# PCB_Capacitor.net
KiCad netlist of a schematic drawn in EAGLE
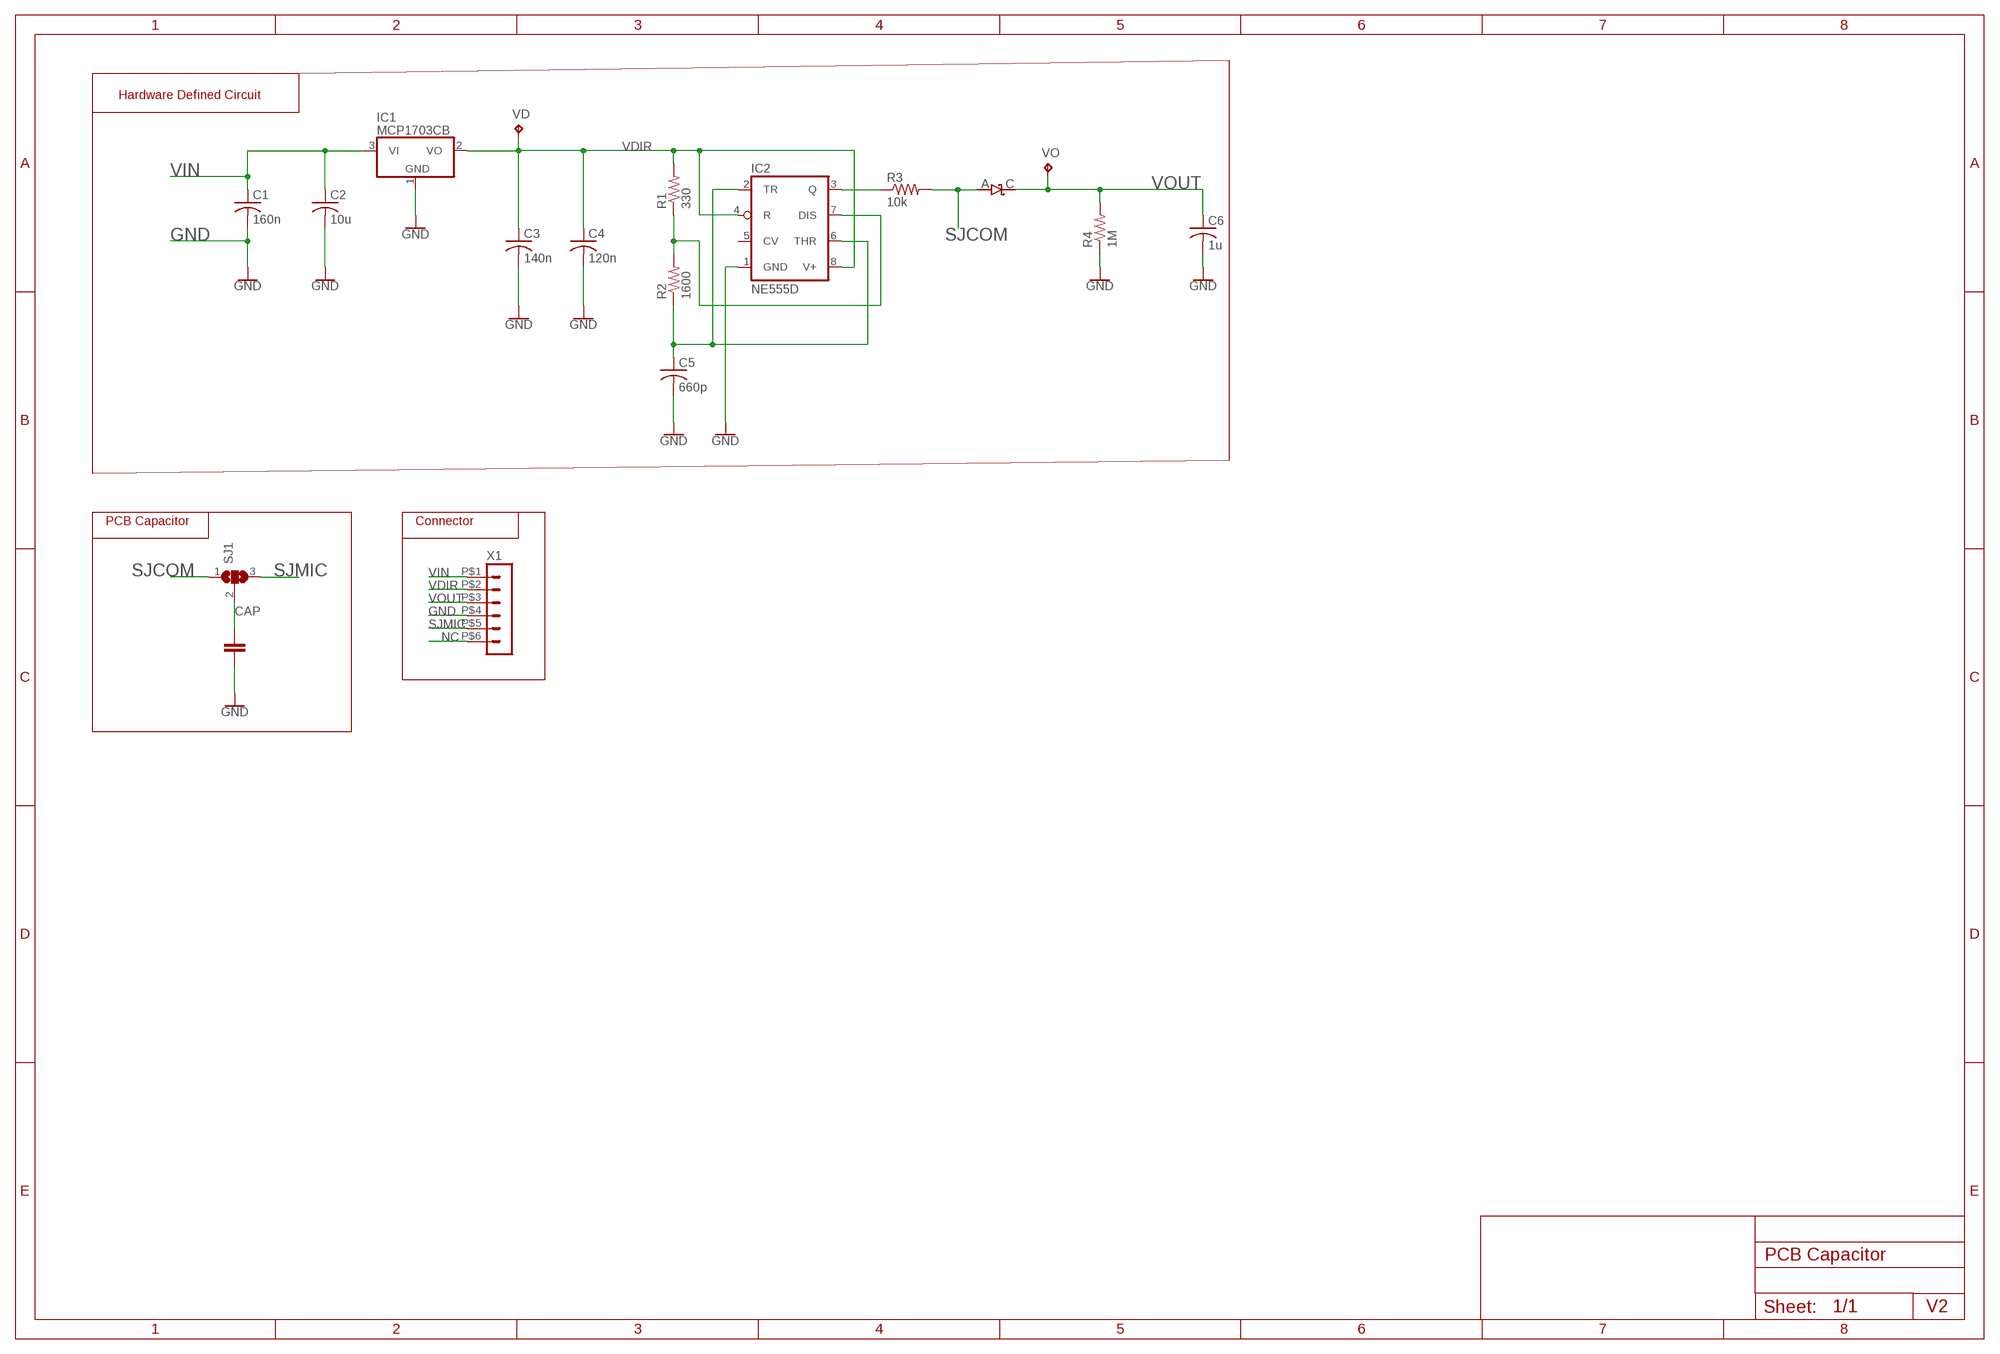
[diagram p0: schematic, sheet 1]

(export (version "E")
  (design (tool "Eeschema 10.0.6"))
  (components
    (comp (ref "C1")
      (value "160n")
      (footprint "eagle-import:C0805")
      (libsource (lib "eagle-import") (part "C-USC0805"))
    )
    (comp (ref "C2")
      (value "10u")
      (footprint "eagle-import:C0805")
      (libsource (lib "eagle-import") (part "C-USC0805"))
    )
    (comp (ref "C3")
      (value "140n")
      (footprint "eagle-import:C0805")
      (libsource (lib "eagle-import") (part "C-USC0805"))
    )
    (comp (ref "C4")
      (value "120n")
      (footprint "eagle-import:C0805")
      (libsource (lib "eagle-import") (part "C-USC0805"))
    )
    (comp (ref "C5")
      (value "660p")
      (footprint "eagle-import:C0805")
      (libsource (lib "eagle-import") (part "C-USC0805"))
    )
    (comp (ref "C6")
      (value "1u")
      (footprint "eagle-import:C0805")
      (libsource (lib "eagle-import") (part "C-USC0805"))
    )
    (comp (ref "D11")
      (value "DIODE_SCHOTTKY_CMMSH2-40")
      (footprint "eagle-import:SOD-123")
      (libsource (lib "eagle-import") (part "DIODE_SCHOTTKY_CMMSH2-40"))
    )
    (comp (ref "IC1")
      (value "MCP1703CB")
      (footprint "eagle-import:SOT23")
      (libsource (lib "eagle-import") (part "MCP1703CB"))
    )
    (comp (ref "IC2")
      (value "NE555D")
      (footprint "eagle-import:SO08")
      (libsource (lib "eagle-import") (part "555DNE"))
    )
    (comp (ref "R1")
      (value "330")
      (footprint "eagle-import:R0603")
      (libsource (lib "eagle-import") (part "R-US_R0603"))
    )
    (comp (ref "R2")
      (value "1600")
      (footprint "eagle-import:R0603")
      (libsource (lib "eagle-import") (part "R-US_R0603"))
    )
    (comp (ref "R3")
      (value "10k")
      (footprint "eagle-import:R0603")
      (libsource (lib "eagle-import") (part "R-US_R0603"))
    )
    (comp (ref "R4")
      (value "1M")
      (footprint "eagle-import:R0603")
      (libsource (lib "eagle-import") (part "R-US_R0603"))
    )
    (comp (ref "SJ1")
      (value "SJ2W")
      (footprint "eagle-import:SJ_2")
      (libsource (lib "eagle-import") (part "SJ2W"))
    )
    (comp (ref "VD")
      (value "TPB1,27")
      (footprint "eagle-import:B1,27")
      (libsource (lib "eagle-import") (part "TPB1,27"))
    )
    (comp (ref "VO")
      (value "TPB1,27")
      (footprint "eagle-import:B1,27")
      (libsource (lib "eagle-import") (part "TPB1,27"))
    )
    (comp (ref "X1")
      (value "HEADER_POS6_43045-0600")
      (footprint "eagle-import:43045-0600")
      (libsource (lib "eagle-import") (part "HEADER_POS6_?43045-0600"))
    )
  )
  (nets
    (net (code "1") (name "/CAP") (class "Default")
      (node (ref "SJ1") (pin "2") (pinfunction "2_2") (pintype "passive"))
    )
    (net (code "2") (name "/NC") (class "Default")
      (node (ref "X1") (pin "P$6") (pinfunction "6_P$6") (pintype "passive"))
    )
    (net (code "3") (name "/SJCOM") (class "Default")
      (node (ref "D11") (pin "A") (pinfunction "A_A") (pintype "bidirectional"))
      (node (ref "R3") (pin "2") (pinfunction "2_2") (pintype "passive"))
      (node (ref "SJ1") (pin "1") (pinfunction "1_1") (pintype "passive"))
    )
    (net (code "4") (name "/SJMIC") (class "Default")
      (node (ref "SJ1") (pin "3") (pinfunction "3_3") (pintype "passive"))
      (node (ref "X1") (pin "P$5") (pinfunction "5_P$5") (pintype "passive"))
    )
    (net (code "5") (name "/VDIR") (class "Default")
      (node (ref "C3") (pin "1") (pinfunction "1_1") (pintype "passive"))
      (node (ref "C4") (pin "1") (pinfunction "1_1") (pintype "passive"))
      (node (ref "IC1") (pin "2") (pinfunction "VO_2") (pintype "passive"))
      (node (ref "IC2") (pin "4") (pinfunction "R_4") (pintype "input"))
      (node (ref "IC2") (pin "8") (pinfunction "V+_8") (pintype "power_in"))
      (node (ref "R1") (pin "2") (pinfunction "2_2") (pintype "passive"))
      (node (ref "VD") (pin "TP") (pinfunction "TP_TP") (pintype "input"))
      (node (ref "X1") (pin "P$2") (pinfunction "2_P$2") (pintype "passive"))
    )
    (net (code "6") (name "/VIN") (class "Default")
      (node (ref "C1") (pin "1") (pinfunction "1_1") (pintype "passive"))
      (node (ref "C2") (pin "1") (pinfunction "1_1") (pintype "passive"))
      (node (ref "IC1") (pin "3") (pinfunction "VI_3") (pintype "input"))
      (node (ref "X1") (pin "P$1") (pinfunction "1_P$1") (pintype "passive"))
    )
    (net (code "7") (name "/VOUT") (class "Default")
      (node (ref "C6") (pin "1") (pinfunction "1_1") (pintype "passive"))
      (node (ref "D11") (pin "C") (pinfunction "C_C") (pintype "bidirectional"))
      (node (ref "R4") (pin "2") (pinfunction "2_2") (pintype "passive"))
      (node (ref "VO") (pin "TP") (pinfunction "TP_TP") (pintype "input"))
      (node (ref "X1") (pin "P$3") (pinfunction "3_P$3") (pintype "passive"))
    )
    (net (code "8") (name "GND") (class "Default")
      (node (ref "C1") (pin "2") (pinfunction "2_2") (pintype "passive"))
      (node (ref "C2") (pin "2") (pinfunction "2_2") (pintype "passive"))
      (node (ref "C3") (pin "2") (pinfunction "2_2") (pintype "passive"))
      (node (ref "C4") (pin "2") (pinfunction "2_2") (pintype "passive"))
      (node (ref "C5") (pin "2") (pinfunction "2_2") (pintype "passive"))
      (node (ref "C6") (pin "2") (pinfunction "2_2") (pintype "passive"))
      (node (ref "IC1") (pin "1") (pinfunction "GND_1") (pintype "passive"))
      (node (ref "IC2") (pin "1") (pinfunction "GND_1") (pintype "power_in"))
      (node (ref "R4") (pin "1") (pinfunction "1_1") (pintype "passive"))
      (node (ref "X1") (pin "P$4") (pinfunction "4_P$4") (pintype "passive"))
    )
    (net (code "9") (name "Net-(IC2-DIS)") (class "Default")
      (node (ref "IC2") (pin "7") (pinfunction "DIS_7") (pintype "input"))
      (node (ref "R1") (pin "1") (pinfunction "1_1") (pintype "passive"))
      (node (ref "R2") (pin "2") (pinfunction "2_2") (pintype "passive"))
    )
    (net (code "10") (name "Net-(IC2-Q)") (class "Default")
      (node (ref "IC2") (pin "3") (pinfunction "Q_3") (pintype "output"))
      (node (ref "R3") (pin "1") (pinfunction "1_1") (pintype "passive"))
    )
    (net (code "11") (name "Net-(IC2-THR)") (class "Default")
      (node (ref "C5") (pin "1") (pinfunction "1_1") (pintype "passive"))
      (node (ref "IC2") (pin "2") (pinfunction "TR_2") (pintype "input"))
      (node (ref "IC2") (pin "6") (pinfunction "THR_6") (pintype "input"))
      (node (ref "R2") (pin "1") (pinfunction "1_1") (pintype "passive"))
    )
    (net (code "12") (name "unconnected-(IC2-CV-Pad5)") (class "Default")
      (node (ref "IC2") (pin "5") (pinfunction "CV_5") (pintype "input"))
    )
  )
)
